# Ninja-towns.net
KiCad netlist of a schematic drawn in EAGLE
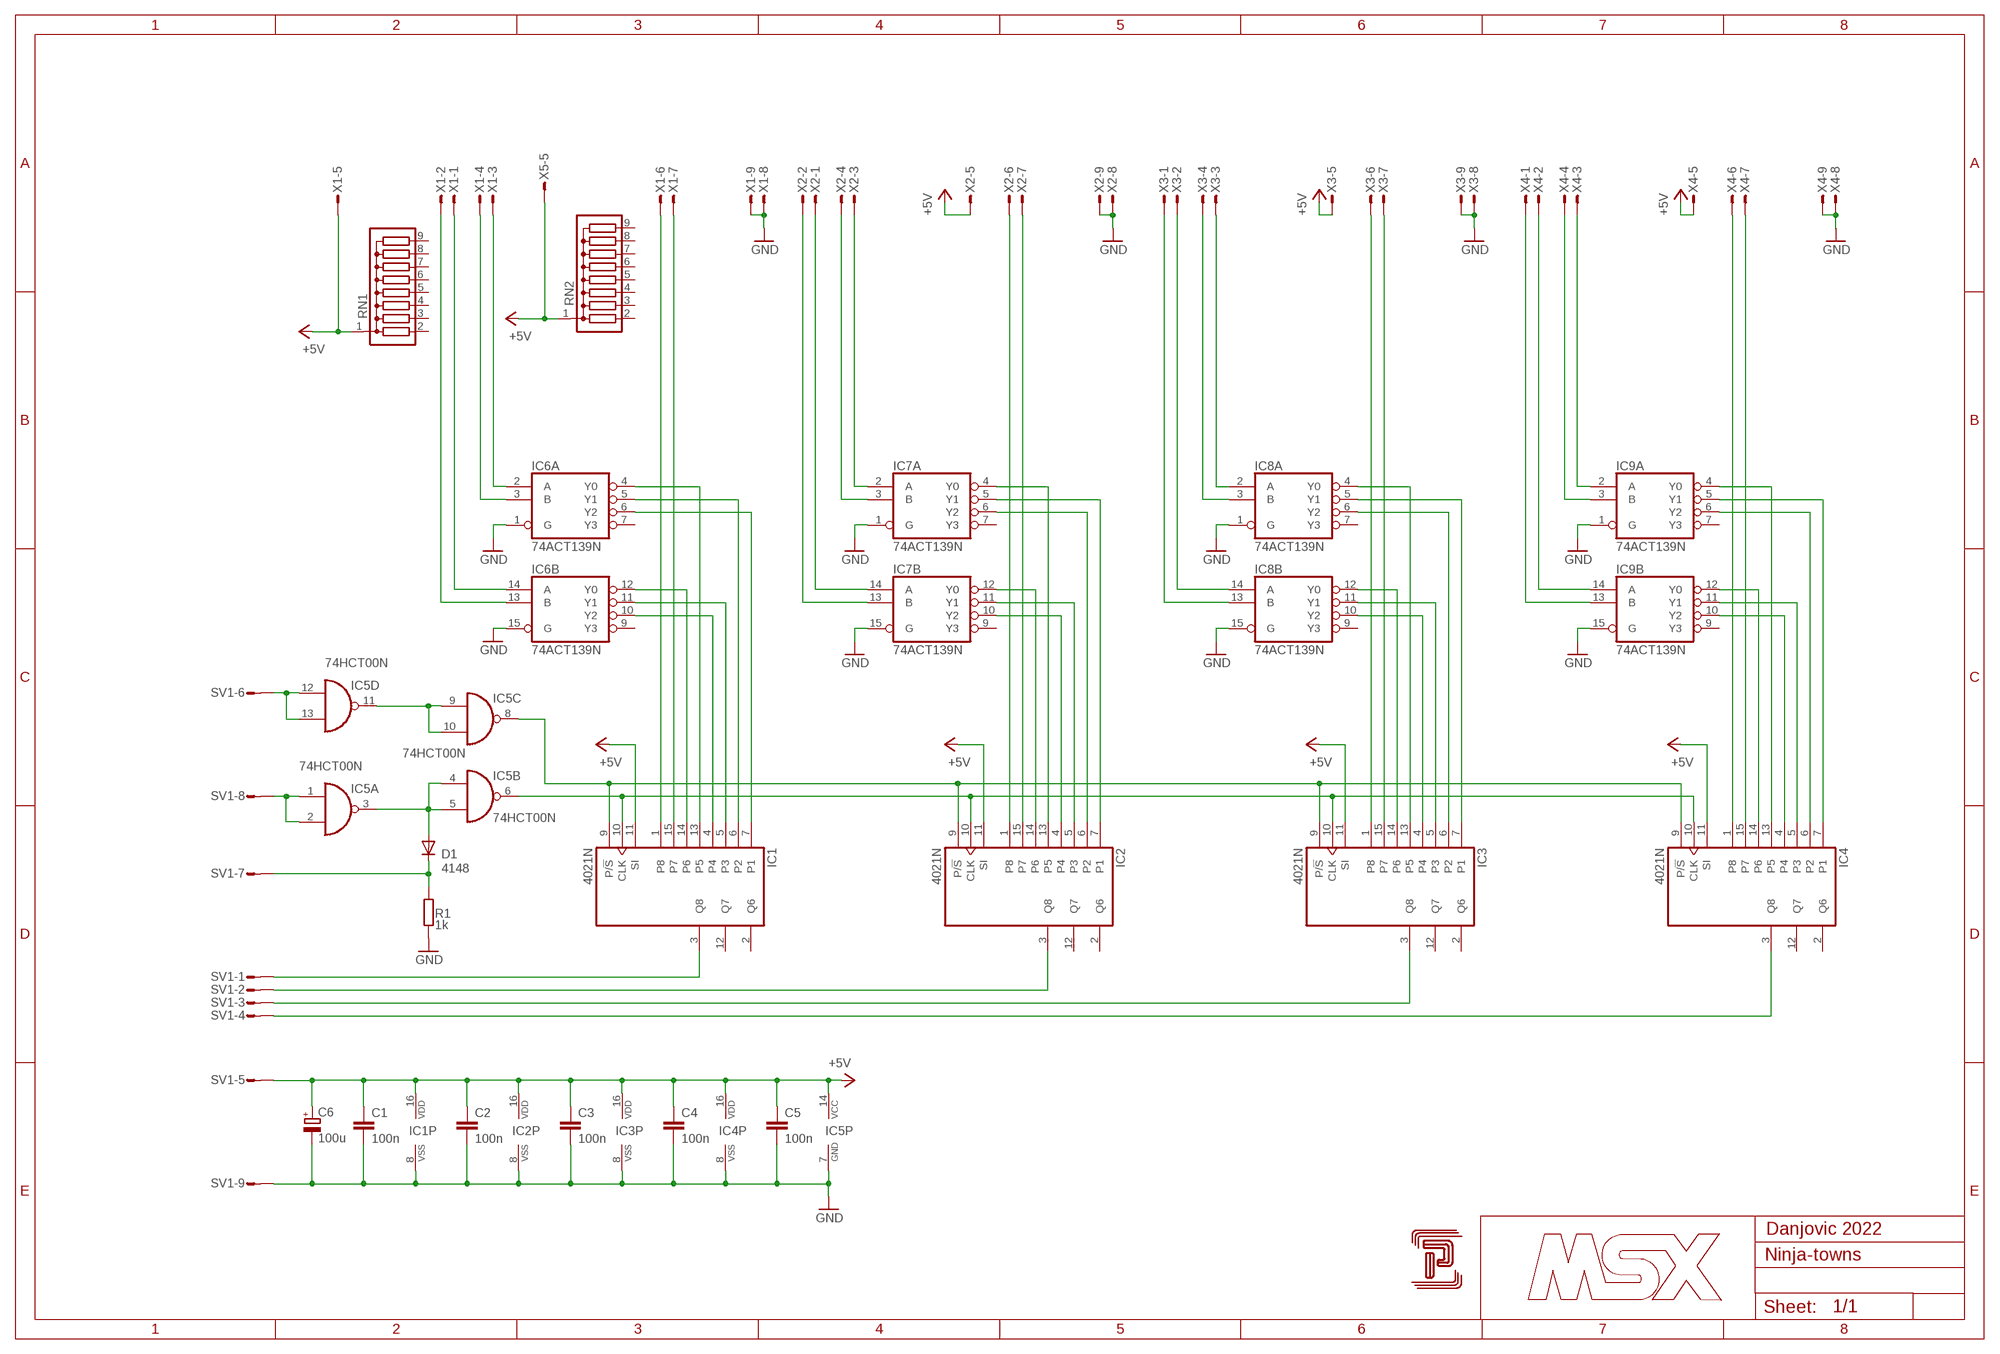
[diagram p0: schematic, sheet 1]

(export (version "E")
  (design (tool "Eeschema 10.0.6"))
  (components
    (comp (ref "C1")
      (value "100n")
      (footprint "eagle-import:C050-024X044")
      (libsource (lib "eagle-import") (part "C-EU050-024X044"))
    )
    (comp (ref "C2")
      (value "100n")
      (footprint "eagle-import:C050-024X044")
      (libsource (lib "eagle-import") (part "C-EU050-024X044"))
    )
    (comp (ref "C3")
      (value "100n")
      (footprint "eagle-import:C050-024X044")
      (libsource (lib "eagle-import") (part "C-EU050-024X044"))
    )
    (comp (ref "C4")
      (value "100n")
      (footprint "eagle-import:C050-024X044")
      (libsource (lib "eagle-import") (part "C-EU050-024X044"))
    )
    (comp (ref "C5")
      (value "100n")
      (footprint "eagle-import:C050-024X044")
      (libsource (lib "eagle-import") (part "C-EU050-024X044"))
    )
    (comp (ref "C6")
      (value "100u")
      (footprint "eagle-import:E2,5-6")
      (libsource (lib "eagle-import") (part "CPOL-EUE2.5-6"))
    )
    (comp (ref "D1")
      (value "4148")
      (footprint "eagle-import:D-5")
      (libsource (lib "eagle-import") (part "DIODE-D-5"))
    )
    (comp (ref "IC1")
      (value "4021N")
      (footprint "eagle-import:DIL16")
      (libsource (lib "eagle-import") (part "4021N"))
    )
    (comp (ref "IC2")
      (value "4021N")
      (footprint "eagle-import:DIL16")
      (libsource (lib "eagle-import") (part "4021N"))
    )
    (comp (ref "IC3")
      (value "4021N")
      (footprint "eagle-import:DIL16")
      (libsource (lib "eagle-import") (part "4021N"))
    )
    (comp (ref "IC4")
      (value "4021N")
      (footprint "eagle-import:DIL16")
      (libsource (lib "eagle-import") (part "4021N"))
    )
    (comp (ref "IC5")
      (value "74HCT00N")
      (footprint "eagle-import:DIL14")
      (libsource (lib "eagle-import") (part "7400NHCT"))
    )
    (comp (ref "IC6")
      (value "74ACT139N")
      (footprint "eagle-import:DIL16")
      (libsource (lib "eagle-import") (part "74139NACT"))
    )
    (comp (ref "IC7")
      (value "74ACT139N")
      (footprint "eagle-import:DIL16")
      (libsource (lib "eagle-import") (part "74139NACT"))
    )
    (comp (ref "IC8")
      (value "74ACT139N")
      (footprint "eagle-import:DIL16")
      (libsource (lib "eagle-import") (part "74139NACT"))
    )
    (comp (ref "IC9")
      (value "74ACT139N")
      (footprint "eagle-import:DIL16")
      (libsource (lib "eagle-import") (part "74139NACT"))
    )
    (comp (ref "R1")
      (value "1k")
      (footprint "eagle-import:0204_7L")
      (libsource (lib "eagle-import") (part "R-EU_0204/7L"))
    )
    (comp (ref "RN1")
      (value "G08R")
      (footprint "eagle-import:SIL9")
      (libsource (lib "eagle-import") (part "G08R"))
    )
    (comp (ref "RN2")
      (value "G08R")
      (footprint "eagle-import:SIL9")
      (libsource (lib "eagle-import") (part "G08R"))
    )
    (comp (ref "SV1")
      (value "S09P")
      (footprint "eagle-import:S09P")
      (libsource (lib "eagle-import") (part "S09P"))
    )
    (comp (ref "U$1")
      (value "PB-202_TOP")
      (footprint "eagle-import:PB202-TOP")
      (libsource (lib "eagle-import") (part "PB-202_TOP"))
    )
    (comp (ref "X1")
      (value "M09-182S")
      (footprint "eagle-import:182-009-MALE")
      (libsource (lib "eagle-import") (part "M09?S-182"))
    )
    (comp (ref "X2")
      (value "M09-182S")
      (footprint "eagle-import:182-009-MALE")
      (libsource (lib "eagle-import") (part "M09?S-182"))
    )
    (comp (ref "X3")
      (value "M09-182S")
      (footprint "eagle-import:182-009-MALE")
      (libsource (lib "eagle-import") (part "M09?S-182"))
    )
    (comp (ref "X4")
      (value "M09-182S")
      (footprint "eagle-import:182-009-MALE")
      (libsource (lib "eagle-import") (part "M09?S-182"))
    )
    (comp (ref "X5")
      (value "M09-182S")
      (footprint "eagle-import:182-009-MALE")
      (libsource (lib "eagle-import") (part "M09?S-182"))
    )
  )
  (nets
    (net (code "1") (name "+5V") (class "Default")
      (node (ref "C1") (pin "1") (pinfunction "1_1") (pintype "passive"))
      (node (ref "C2") (pin "1") (pinfunction "1_1") (pintype "passive"))
      (node (ref "C3") (pin "1") (pinfunction "1_1") (pintype "passive"))
      (node (ref "C4") (pin "1") (pinfunction "1_1") (pintype "passive"))
      (node (ref "C5") (pin "1") (pinfunction "1_1") (pintype "passive"))
      (node (ref "C6") (pin "+") (pinfunction "+_+") (pintype "passive"))
      (node (ref "IC1") (pin "11") (pinfunction "SI_11") (pintype "input"))
      (node (ref "IC1") (pin "16") (pinfunction "VDD_16") (pintype "power_in"))
      (node (ref "IC2") (pin "11") (pinfunction "SI_11") (pintype "input"))
      (node (ref "IC2") (pin "16") (pinfunction "VDD_16") (pintype "power_in"))
      (node (ref "IC3") (pin "11") (pinfunction "SI_11") (pintype "input"))
      (node (ref "IC3") (pin "16") (pinfunction "VDD_16") (pintype "power_in"))
      (node (ref "IC4") (pin "11") (pinfunction "SI_11") (pintype "input"))
      (node (ref "IC4") (pin "16") (pinfunction "VDD_16") (pintype "power_in"))
      (node (ref "IC5") (pin "14") (pinfunction "VCC_14") (pintype "power_in"))
      (node (ref "RN1") (pin "1") (pinfunction "1_1") (pintype "passive"))
      (node (ref "RN2") (pin "1") (pinfunction "1_1") (pintype "passive"))
      (node (ref "SV1") (pin "5") (pinfunction "S_5") (pintype "passive"))
      (node (ref "X1") (pin "5") (pinfunction "M_5") (pintype "passive"))
      (node (ref "X2") (pin "5") (pinfunction "M_5") (pintype "passive"))
      (node (ref "X3") (pin "5") (pinfunction "M_5") (pintype "passive"))
      (node (ref "X4") (pin "5") (pinfunction "M_5") (pintype "passive"))
      (node (ref "X5") (pin "5") (pinfunction "M_5") (pintype "passive"))
    )
    (net (code "2") (name "GND") (class "Default")
      (node (ref "C1") (pin "2") (pinfunction "2_2") (pintype "passive"))
      (node (ref "C2") (pin "2") (pinfunction "2_2") (pintype "passive"))
      (node (ref "C3") (pin "2") (pinfunction "2_2") (pintype "passive"))
      (node (ref "C4") (pin "2") (pinfunction "2_2") (pintype "passive"))
      (node (ref "C5") (pin "2") (pinfunction "2_2") (pintype "passive"))
      (node (ref "C6") (pin "-") (pinfunction "-_-") (pintype "passive"))
      (node (ref "IC1") (pin "8") (pinfunction "VSS_8") (pintype "power_in"))
      (node (ref "IC2") (pin "8") (pinfunction "VSS_8") (pintype "power_in"))
      (node (ref "IC3") (pin "8") (pinfunction "VSS_8") (pintype "power_in"))
      (node (ref "IC4") (pin "8") (pinfunction "VSS_8") (pintype "power_in"))
      (node (ref "IC5") (pin "7") (pinfunction "GND_7") (pintype "power_in"))
      (node (ref "IC6") (pin "1") (pinfunction "G_1") (pintype "input"))
      (node (ref "IC6") (pin "15") (pinfunction "G_15") (pintype "input"))
      (node (ref "IC7") (pin "1") (pinfunction "G_1") (pintype "input"))
      (node (ref "IC7") (pin "15") (pinfunction "G_15") (pintype "input"))
      (node (ref "IC8") (pin "1") (pinfunction "G_1") (pintype "input"))
      (node (ref "IC8") (pin "15") (pinfunction "G_15") (pintype "input"))
      (node (ref "IC9") (pin "1") (pinfunction "G_1") (pintype "input"))
      (node (ref "IC9") (pin "15") (pinfunction "G_15") (pintype "input"))
      (node (ref "R1") (pin "1") (pinfunction "1_1") (pintype "passive"))
      (node (ref "SV1") (pin "9") (pinfunction "S_9") (pintype "passive"))
      (node (ref "X1") (pin "8") (pinfunction "M_8") (pintype "passive"))
      (node (ref "X1") (pin "9") (pinfunction "M_9") (pintype "passive"))
      (node (ref "X2") (pin "8") (pinfunction "M_8") (pintype "passive"))
      (node (ref "X2") (pin "9") (pinfunction "M_9") (pintype "passive"))
      (node (ref "X3") (pin "8") (pinfunction "M_8") (pintype "passive"))
      (node (ref "X3") (pin "9") (pinfunction "M_9") (pintype "passive"))
      (node (ref "X4") (pin "8") (pinfunction "M_8") (pintype "passive"))
      (node (ref "X4") (pin "9") (pinfunction "M_9") (pintype "passive"))
    )
    (net (code "3") (name "Net-(IC1A-CLK)") (class "Default")
      (node (ref "IC1") (pin "10") (pinfunction "CLK_10") (pintype "input"))
      (node (ref "IC2") (pin "10") (pinfunction "CLK_10") (pintype "input"))
      (node (ref "IC3") (pin "10") (pinfunction "CLK_10") (pintype "input"))
      (node (ref "IC4") (pin "10") (pinfunction "CLK_10") (pintype "input"))
      (node (ref "IC5") (pin "6") (pinfunction "O_6") (pintype "output"))
    )
    (net (code "4") (name "Net-(IC1A-P1)") (class "Default")
      (node (ref "IC1") (pin "7") (pinfunction "P1_7") (pintype "input"))
      (node (ref "IC6") (pin "6") (pinfunction "Y2_6") (pintype "output"))
    )
    (net (code "5") (name "Net-(IC1A-P2)") (class "Default")
      (node (ref "IC1") (pin "6") (pinfunction "P2_6") (pintype "input"))
      (node (ref "IC6") (pin "5") (pinfunction "Y1_5") (pintype "output"))
    )
    (net (code "6") (name "Net-(IC1A-P3)") (class "Default")
      (node (ref "IC1") (pin "5") (pinfunction "P3_5") (pintype "input"))
      (node (ref "IC6") (pin "11") (pinfunction "Y1_11") (pintype "output"))
    )
    (net (code "7") (name "Net-(IC1A-P4)") (class "Default")
      (node (ref "IC1") (pin "4") (pinfunction "P4_4") (pintype "input"))
      (node (ref "IC6") (pin "10") (pinfunction "Y2_10") (pintype "output"))
    )
    (net (code "8") (name "Net-(IC1A-P5)") (class "Default")
      (node (ref "IC1") (pin "13") (pinfunction "P5_13") (pintype "input"))
      (node (ref "IC6") (pin "4") (pinfunction "Y0_4") (pintype "output"))
    )
    (net (code "9") (name "Net-(IC1A-P6)") (class "Default")
      (node (ref "IC1") (pin "14") (pinfunction "P6_14") (pintype "input"))
      (node (ref "IC6") (pin "12") (pinfunction "Y0_12") (pintype "output"))
    )
    (net (code "10") (name "Net-(IC1A-P7)") (class "Default")
      (node (ref "IC1") (pin "15") (pinfunction "P7_15") (pintype "input"))
      (node (ref "X1") (pin "7") (pinfunction "M_7") (pintype "passive"))
    )
    (net (code "11") (name "Net-(IC1A-P8)") (class "Default")
      (node (ref "IC1") (pin "1") (pinfunction "P8_1") (pintype "input"))
      (node (ref "X1") (pin "6") (pinfunction "M_6") (pintype "passive"))
    )
    (net (code "12") (name "Net-(IC1A-P{slash}~{S})") (class "Default")
      (node (ref "IC1") (pin "9") (pinfunction "P/~{S}_9") (pintype "input"))
      (node (ref "IC2") (pin "9") (pinfunction "P/~{S}_9") (pintype "input"))
      (node (ref "IC3") (pin "9") (pinfunction "P/~{S}_9") (pintype "input"))
      (node (ref "IC4") (pin "9") (pinfunction "P/~{S}_9") (pintype "input"))
      (node (ref "IC5") (pin "8") (pinfunction "O_8") (pintype "output"))
    )
    (net (code "13") (name "Net-(IC1A-Q8)") (class "Default")
      (node (ref "IC1") (pin "3") (pinfunction "Q8_3") (pintype "output"))
      (node (ref "SV1") (pin "1") (pinfunction "S_1") (pintype "passive"))
    )
    (net (code "14") (name "Net-(IC2A-P1)") (class "Default")
      (node (ref "IC2") (pin "7") (pinfunction "P1_7") (pintype "input"))
      (node (ref "IC7") (pin "5") (pinfunction "Y1_5") (pintype "output"))
    )
    (net (code "15") (name "Net-(IC2A-P2)") (class "Default")
      (node (ref "IC2") (pin "6") (pinfunction "P2_6") (pintype "input"))
      (node (ref "IC7") (pin "6") (pinfunction "Y2_6") (pintype "output"))
    )
    (net (code "16") (name "Net-(IC2A-P3)") (class "Default")
      (node (ref "IC2") (pin "5") (pinfunction "P3_5") (pintype "input"))
      (node (ref "IC7") (pin "11") (pinfunction "Y1_11") (pintype "output"))
    )
    (net (code "17") (name "Net-(IC2A-P4)") (class "Default")
      (node (ref "IC2") (pin "4") (pinfunction "P4_4") (pintype "input"))
      (node (ref "IC7") (pin "10") (pinfunction "Y2_10") (pintype "output"))
    )
    (net (code "18") (name "Net-(IC2A-P5)") (class "Default")
      (node (ref "IC2") (pin "13") (pinfunction "P5_13") (pintype "input"))
      (node (ref "IC7") (pin "4") (pinfunction "Y0_4") (pintype "output"))
    )
    (net (code "19") (name "Net-(IC2A-P6)") (class "Default")
      (node (ref "IC2") (pin "14") (pinfunction "P6_14") (pintype "input"))
      (node (ref "IC7") (pin "12") (pinfunction "Y0_12") (pintype "output"))
    )
    (net (code "20") (name "Net-(IC2A-P7)") (class "Default")
      (node (ref "IC2") (pin "15") (pinfunction "P7_15") (pintype "input"))
      (node (ref "X2") (pin "7") (pinfunction "M_7") (pintype "passive"))
    )
    (net (code "21") (name "Net-(IC2A-P8)") (class "Default")
      (node (ref "IC2") (pin "1") (pinfunction "P8_1") (pintype "input"))
      (node (ref "X2") (pin "6") (pinfunction "M_6") (pintype "passive"))
    )
    (net (code "22") (name "Net-(IC2A-Q8)") (class "Default")
      (node (ref "IC2") (pin "3") (pinfunction "Q8_3") (pintype "output"))
      (node (ref "SV1") (pin "2") (pinfunction "S_2") (pintype "passive"))
    )
    (net (code "23") (name "Net-(IC3A-P1)") (class "Default")
      (node (ref "IC3") (pin "7") (pinfunction "P1_7") (pintype "input"))
      (node (ref "IC8") (pin "5") (pinfunction "Y1_5") (pintype "output"))
    )
    (net (code "24") (name "Net-(IC3A-P2)") (class "Default")
      (node (ref "IC3") (pin "6") (pinfunction "P2_6") (pintype "input"))
      (node (ref "IC8") (pin "6") (pinfunction "Y2_6") (pintype "output"))
    )
    (net (code "25") (name "Net-(IC3A-P3)") (class "Default")
      (node (ref "IC3") (pin "5") (pinfunction "P3_5") (pintype "input"))
      (node (ref "IC8") (pin "11") (pinfunction "Y1_11") (pintype "output"))
    )
    (net (code "26") (name "Net-(IC3A-P4)") (class "Default")
      (node (ref "IC3") (pin "4") (pinfunction "P4_4") (pintype "input"))
      (node (ref "IC8") (pin "10") (pinfunction "Y2_10") (pintype "output"))
    )
    (net (code "27") (name "Net-(IC3A-P5)") (class "Default")
      (node (ref "IC3") (pin "13") (pinfunction "P5_13") (pintype "input"))
      (node (ref "IC8") (pin "4") (pinfunction "Y0_4") (pintype "output"))
    )
    (net (code "28") (name "Net-(IC3A-P6)") (class "Default")
      (node (ref "IC3") (pin "14") (pinfunction "P6_14") (pintype "input"))
      (node (ref "IC8") (pin "12") (pinfunction "Y0_12") (pintype "output"))
    )
    (net (code "29") (name "Net-(IC3A-P7)") (class "Default")
      (node (ref "IC3") (pin "15") (pinfunction "P7_15") (pintype "input"))
      (node (ref "X3") (pin "7") (pinfunction "M_7") (pintype "passive"))
    )
    (net (code "30") (name "Net-(IC3A-P8)") (class "Default")
      (node (ref "IC3") (pin "1") (pinfunction "P8_1") (pintype "input"))
      (node (ref "X3") (pin "6") (pinfunction "M_6") (pintype "passive"))
    )
    (net (code "31") (name "Net-(IC3A-Q8)") (class "Default")
      (node (ref "IC3") (pin "3") (pinfunction "Q8_3") (pintype "output"))
      (node (ref "SV1") (pin "3") (pinfunction "S_3") (pintype "passive"))
    )
    (net (code "32") (name "Net-(IC4A-P1)") (class "Default")
      (node (ref "IC4") (pin "7") (pinfunction "P1_7") (pintype "input"))
      (node (ref "IC9") (pin "5") (pinfunction "Y1_5") (pintype "output"))
    )
    (net (code "33") (name "Net-(IC4A-P2)") (class "Default")
      (node (ref "IC4") (pin "6") (pinfunction "P2_6") (pintype "input"))
      (node (ref "IC9") (pin "6") (pinfunction "Y2_6") (pintype "output"))
    )
    (net (code "34") (name "Net-(IC4A-P3)") (class "Default")
      (node (ref "IC4") (pin "5") (pinfunction "P3_5") (pintype "input"))
      (node (ref "IC9") (pin "11") (pinfunction "Y1_11") (pintype "output"))
    )
    (net (code "35") (name "Net-(IC4A-P4)") (class "Default")
      (node (ref "IC4") (pin "4") (pinfunction "P4_4") (pintype "input"))
      (node (ref "IC9") (pin "10") (pinfunction "Y2_10") (pintype "output"))
    )
    (net (code "36") (name "Net-(IC4A-P5)") (class "Default")
      (node (ref "IC4") (pin "13") (pinfunction "P5_13") (pintype "input"))
      (node (ref "IC9") (pin "4") (pinfunction "Y0_4") (pintype "output"))
    )
    (net (code "37") (name "Net-(IC4A-P6)") (class "Default")
      (node (ref "IC4") (pin "14") (pinfunction "P6_14") (pintype "input"))
      (node (ref "IC9") (pin "12") (pinfunction "Y0_12") (pintype "output"))
    )
    (net (code "38") (name "Net-(IC4A-P7)") (class "Default")
      (node (ref "IC4") (pin "15") (pinfunction "P7_15") (pintype "input"))
      (node (ref "X4") (pin "7") (pinfunction "M_7") (pintype "passive"))
    )
    (net (code "39") (name "Net-(IC4A-P8)") (class "Default")
      (node (ref "IC4") (pin "1") (pinfunction "P8_1") (pintype "input"))
      (node (ref "X4") (pin "6") (pinfunction "M_6") (pintype "passive"))
    )
    (net (code "40") (name "Net-(IC4A-Q8)") (class "Default")
      (node (ref "IC4") (pin "3") (pinfunction "Q8_3") (pintype "output"))
      (node (ref "SV1") (pin "4") (pinfunction "S_4") (pintype "passive"))
    )
    (net (code "41") (name "Net-(IC5A-I0)") (class "Default")
      (node (ref "IC5") (pin "1") (pinfunction "I0_1") (pintype "input"))
      (node (ref "IC5") (pin "2") (pinfunction "I1_2") (pintype "input"))
      (node (ref "SV1") (pin "8") (pinfunction "S_8") (pintype "passive"))
    )
    (net (code "42") (name "Net-(IC5A-O)") (class "Default")
      (node (ref "D1") (pin "A") (pinfunction "A_A") (pintype "passive"))
      (node (ref "IC5") (pin "3") (pinfunction "O_3") (pintype "output"))
      (node (ref "IC5") (pin "4") (pinfunction "I0_4") (pintype "input"))
      (node (ref "IC5") (pin "5") (pinfunction "I1_5") (pintype "input"))
    )
    (net (code "43") (name "Net-(IC5C-I0)") (class "Default")
      (node (ref "IC5") (pin "10") (pinfunction "I1_10") (pintype "input"))
      (node (ref "IC5") (pin "11") (pinfunction "O_11") (pintype "output"))
      (node (ref "IC5") (pin "9") (pinfunction "I0_9") (pintype "input"))
    )
    (net (code "44") (name "Net-(IC5D-I0)") (class "Default")
      (node (ref "IC5") (pin "12") (pinfunction "I0_12") (pintype "input"))
      (node (ref "IC5") (pin "13") (pinfunction "I1_13") (pintype "input"))
      (node (ref "SV1") (pin "6") (pinfunction "S_6") (pintype "passive"))
    )
    (net (code "45") (name "Net-(IC6A-A)") (class "Default")
      (node (ref "IC6") (pin "2") (pinfunction "A_2") (pintype "input"))
      (node (ref "X1") (pin "3") (pinfunction "M_3") (pintype "passive"))
    )
    (net (code "46") (name "Net-(IC6A-B)") (class "Default")
      (node (ref "IC6") (pin "3") (pinfunction "B_3") (pintype "input"))
      (node (ref "X1") (pin "4") (pinfunction "M_4") (pintype "passive"))
    )
    (net (code "47") (name "Net-(IC6B-A)") (class "Default")
      (node (ref "IC6") (pin "14") (pinfunction "A_14") (pintype "input"))
      (node (ref "X1") (pin "1") (pinfunction "M_1") (pintype "passive"))
    )
    (net (code "48") (name "Net-(IC6B-B)") (class "Default")
      (node (ref "IC6") (pin "13") (pinfunction "B_13") (pintype "input"))
      (node (ref "X1") (pin "2") (pinfunction "M_2") (pintype "passive"))
    )
    (net (code "49") (name "Net-(IC7A-A)") (class "Default")
      (node (ref "IC7") (pin "2") (pinfunction "A_2") (pintype "input"))
      (node (ref "X2") (pin "3") (pinfunction "M_3") (pintype "passive"))
    )
    (net (code "50") (name "Net-(IC7A-B)") (class "Default")
      (node (ref "IC7") (pin "3") (pinfunction "B_3") (pintype "input"))
      (node (ref "X2") (pin "4") (pinfunction "M_4") (pintype "passive"))
    )
    (net (code "51") (name "Net-(IC7B-A)") (class "Default")
      (node (ref "IC7") (pin "14") (pinfunction "A_14") (pintype "input"))
      (node (ref "X2") (pin "1") (pinfunction "M_1") (pintype "passive"))
    )
    (net (code "52") (name "Net-(IC7B-B)") (class "Default")
      (node (ref "IC7") (pin "13") (pinfunction "B_13") (pintype "input"))
      (node (ref "X2") (pin "2") (pinfunction "M_2") (pintype "passive"))
    )
    (net (code "53") (name "Net-(IC8A-A)") (class "Default")
      (node (ref "IC8") (pin "2") (pinfunction "A_2") (pintype "input"))
      (node (ref "X3") (pin "3") (pinfunction "M_3") (pintype "passive"))
    )
    (net (code "54") (name "Net-(IC8A-B)") (class "Default")
      (node (ref "IC8") (pin "3") (pinfunction "B_3") (pintype "input"))
      (node (ref "X3") (pin "4") (pinfunction "M_4") (pintype "passive"))
    )
    (net (code "55") (name "Net-(IC8B-A)") (class "Default")
      (node (ref "IC8") (pin "14") (pinfunction "A_14") (pintype "input"))
      (node (ref "X3") (pin "2") (pinfunction "M_2") (pintype "passive"))
    )
    (net (code "56") (name "Net-(IC8B-B)") (class "Default")
      (node (ref "IC8") (pin "13") (pinfunction "B_13") (pintype "input"))
      (node (ref "X3") (pin "1") (pinfunction "M_1") (pintype "passive"))
    )
    (net (code "57") (name "Net-(IC9A-A)") (class "Default")
      (node (ref "IC9") (pin "2") (pinfunction "A_2") (pintype "input"))
      (node (ref "X4") (pin "3") (pinfunction "M_3") (pintype "passive"))
    )
    (net (code "58") (name "Net-(IC9A-B)") (class "Default")
      (node (ref "IC9") (pin "3") (pinfunction "B_3") (pintype "input"))
      (node (ref "X4") (pin "4") (pinfunction "M_4") (pintype "passive"))
    )
    (net (code "59") (name "Net-(IC9B-A)") (class "Default")
      (node (ref "IC9") (pin "14") (pinfunction "A_14") (pintype "input"))
      (node (ref "X4") (pin "2") (pinfunction "M_2") (pintype "passive"))
    )
    (net (code "60") (name "Net-(IC9B-B)") (class "Default")
      (node (ref "IC9") (pin "13") (pinfunction "B_13") (pintype "input"))
      (node (ref "X4") (pin "1") (pinfunction "M_1") (pintype "passive"))
    )
    (net (code "61") (name "Net-(SV1G-S)") (class "Default")
      (node (ref "D1") (pin "C") (pinfunction "C_C") (pintype "passive"))
      (node (ref "R1") (pin "2") (pinfunction "2_2") (pintype "passive"))
      (node (ref "SV1") (pin "7") (pinfunction "S_7") (pintype "passive"))
    )
    (net (code "62") (name "unconnected-(IC1A-Q6-Pad2)") (class "Default")
      (node (ref "IC1") (pin "2") (pinfunction "Q6_2") (pintype "output"))
    )
    (net (code "63") (name "unconnected-(IC1A-Q7-Pad12)") (class "Default")
      (node (ref "IC1") (pin "12") (pinfunction "Q7_12") (pintype "output"))
    )
    (net (code "64") (name "unconnected-(IC2A-Q6-Pad2)") (class "Default")
      (node (ref "IC2") (pin "2") (pinfunction "Q6_2") (pintype "output"))
    )
    (net (code "65") (name "unconnected-(IC2A-Q7-Pad12)") (class "Default")
      (node (ref "IC2") (pin "12") (pinfunction "Q7_12") (pintype "output"))
    )
    (net (code "66") (name "unconnected-(IC3A-Q6-Pad2)") (class "Default")
      (node (ref "IC3") (pin "2") (pinfunction "Q6_2") (pintype "output"))
    )
    (net (code "67") (name "unconnected-(IC3A-Q7-Pad12)") (class "Default")
      (node (ref "IC3") (pin "12") (pinfunction "Q7_12") (pintype "output"))
    )
    (net (code "68") (name "unconnected-(IC4A-Q6-Pad2)") (class "Default")
      (node (ref "IC4") (pin "2") (pinfunction "Q6_2") (pintype "output"))
    )
    (net (code "69") (name "unconnected-(IC4A-Q7-Pad12)") (class "Default")
      (node (ref "IC4") (pin "12") (pinfunction "Q7_12") (pintype "output"))
    )
    (net (code "70") (name "unconnected-(IC6A-Y3-Pad7)") (class "Default")
      (node (ref "IC6") (pin "7") (pinfunction "Y3_7") (pintype "output"))
    )
    (net (code "71") (name "unconnected-(IC6B-Y3-Pad9)") (class "Default")
      (node (ref "IC6") (pin "9") (pinfunction "Y3_9") (pintype "output"))
    )
    (net (code "72") (name "unconnected-(IC7A-Y3-Pad7)") (class "Default")
      (node (ref "IC7") (pin "7") (pinfunction "Y3_7") (pintype "output"))
    )
    (net (code "73") (name "unconnected-(IC7B-Y3-Pad9)") (class "Default")
      (node (ref "IC7") (pin "9") (pinfunction "Y3_9") (pintype "output"))
    )
    (net (code "74") (name "unconnected-(IC8A-Y3-Pad7)") (class "Default")
      (node (ref "IC8") (pin "7") (pinfunction "Y3_7") (pintype "output"))
    )
    (net (code "75") (name "unconnected-(IC8B-Y3-Pad9)") (class "Default")
      (node (ref "IC8") (pin "9") (pinfunction "Y3_9") (pintype "output"))
    )
    (net (code "76") (name "unconnected-(IC9A-Y3-Pad7)") (class "Default")
      (node (ref "IC9") (pin "7") (pinfunction "Y3_7") (pintype "output"))
    )
    (net (code "77") (name "unconnected-(IC9B-Y3-Pad9)") (class "Default")
      (node (ref "IC9") (pin "9") (pinfunction "Y3_9") (pintype "output"))
    )
    (net (code "78") (name "unconnected-(RN1-Pad2)") (class "Default")
      (node (ref "RN1") (pin "2") (pinfunction "2_2") (pintype "passive"))
    )
    (net (code "79") (name "unconnected-(RN1-Pad3)") (class "Default")
      (node (ref "RN1") (pin "3") (pinfunction "3_3") (pintype "passive"))
    )
    (net (code "80") (name "unconnected-(RN1-Pad4)") (class "Default")
      (node (ref "RN1") (pin "4") (pinfunction "4_4") (pintype "passive"))
    )
    (net (code "81") (name "unconnected-(RN1-Pad5)") (class "Default")
      (node (ref "RN1") (pin "5") (pinfunction "5_5") (pintype "passive"))
    )
    (net (code "82") (name "unconnected-(RN1-Pad6)") (class "Default")
      (node (ref "RN1") (pin "6") (pinfunction "6_6") (pintype "passive"))
    )
    (net (code "83") (name "unconnected-(RN1-Pad7)") (class "Default")
      (node (ref "RN1") (pin "7") (pinfunction "7_7") (pintype "passive"))
    )
    (net (code "84") (name "unconnected-(RN1-Pad8)") (class "Default")
      (node (ref "RN1") (pin "8") (pinfunction "8_8") (pintype "passive"))
    )
    (net (code "85") (name "unconnected-(RN1-Pad9)") (class "Default")
      (node (ref "RN1") (pin "9") (pinfunction "9_9") (pintype "passive"))
    )
    (net (code "86") (name "unconnected-(RN2-Pad2)") (class "Default")
      (node (ref "RN2") (pin "2") (pinfunction "2_2") (pintype "passive"))
    )
    (net (code "87") (name "unconnected-(RN2-Pad3)") (class "Default")
      (node (ref "RN2") (pin "3") (pinfunction "3_3") (pintype "passive"))
    )
    (net (code "88") (name "unconnected-(RN2-Pad4)") (class "Default")
      (node (ref "RN2") (pin "4") (pinfunction "4_4") (pintype "passive"))
    )
    (net (code "89") (name "unconnected-(RN2-Pad5)") (class "Default")
      (node (ref "RN2") (pin "5") (pinfunction "5_5") (pintype "passive"))
    )
    (net (code "90") (name "unconnected-(RN2-Pad6)") (class "Default")
      (node (ref "RN2") (pin "6") (pinfunction "6_6") (pintype "passive"))
    )
    (net (code "91") (name "unconnected-(RN2-Pad7)") (class "Default")
      (node (ref "RN2") (pin "7") (pinfunction "7_7") (pintype "passive"))
    )
    (net (code "92") (name "unconnected-(RN2-Pad8)") (class "Default")
      (node (ref "RN2") (pin "8") (pinfunction "8_8") (pintype "passive"))
    )
    (net (code "93") (name "unconnected-(RN2-Pad9)") (class "Default")
      (node (ref "RN2") (pin "9") (pinfunction "9_9") (pintype "passive"))
    )
  )
)
